# Arduino_Basic_Sensor_Board.net
KiCad netlist of a schematic drawn in EAGLE
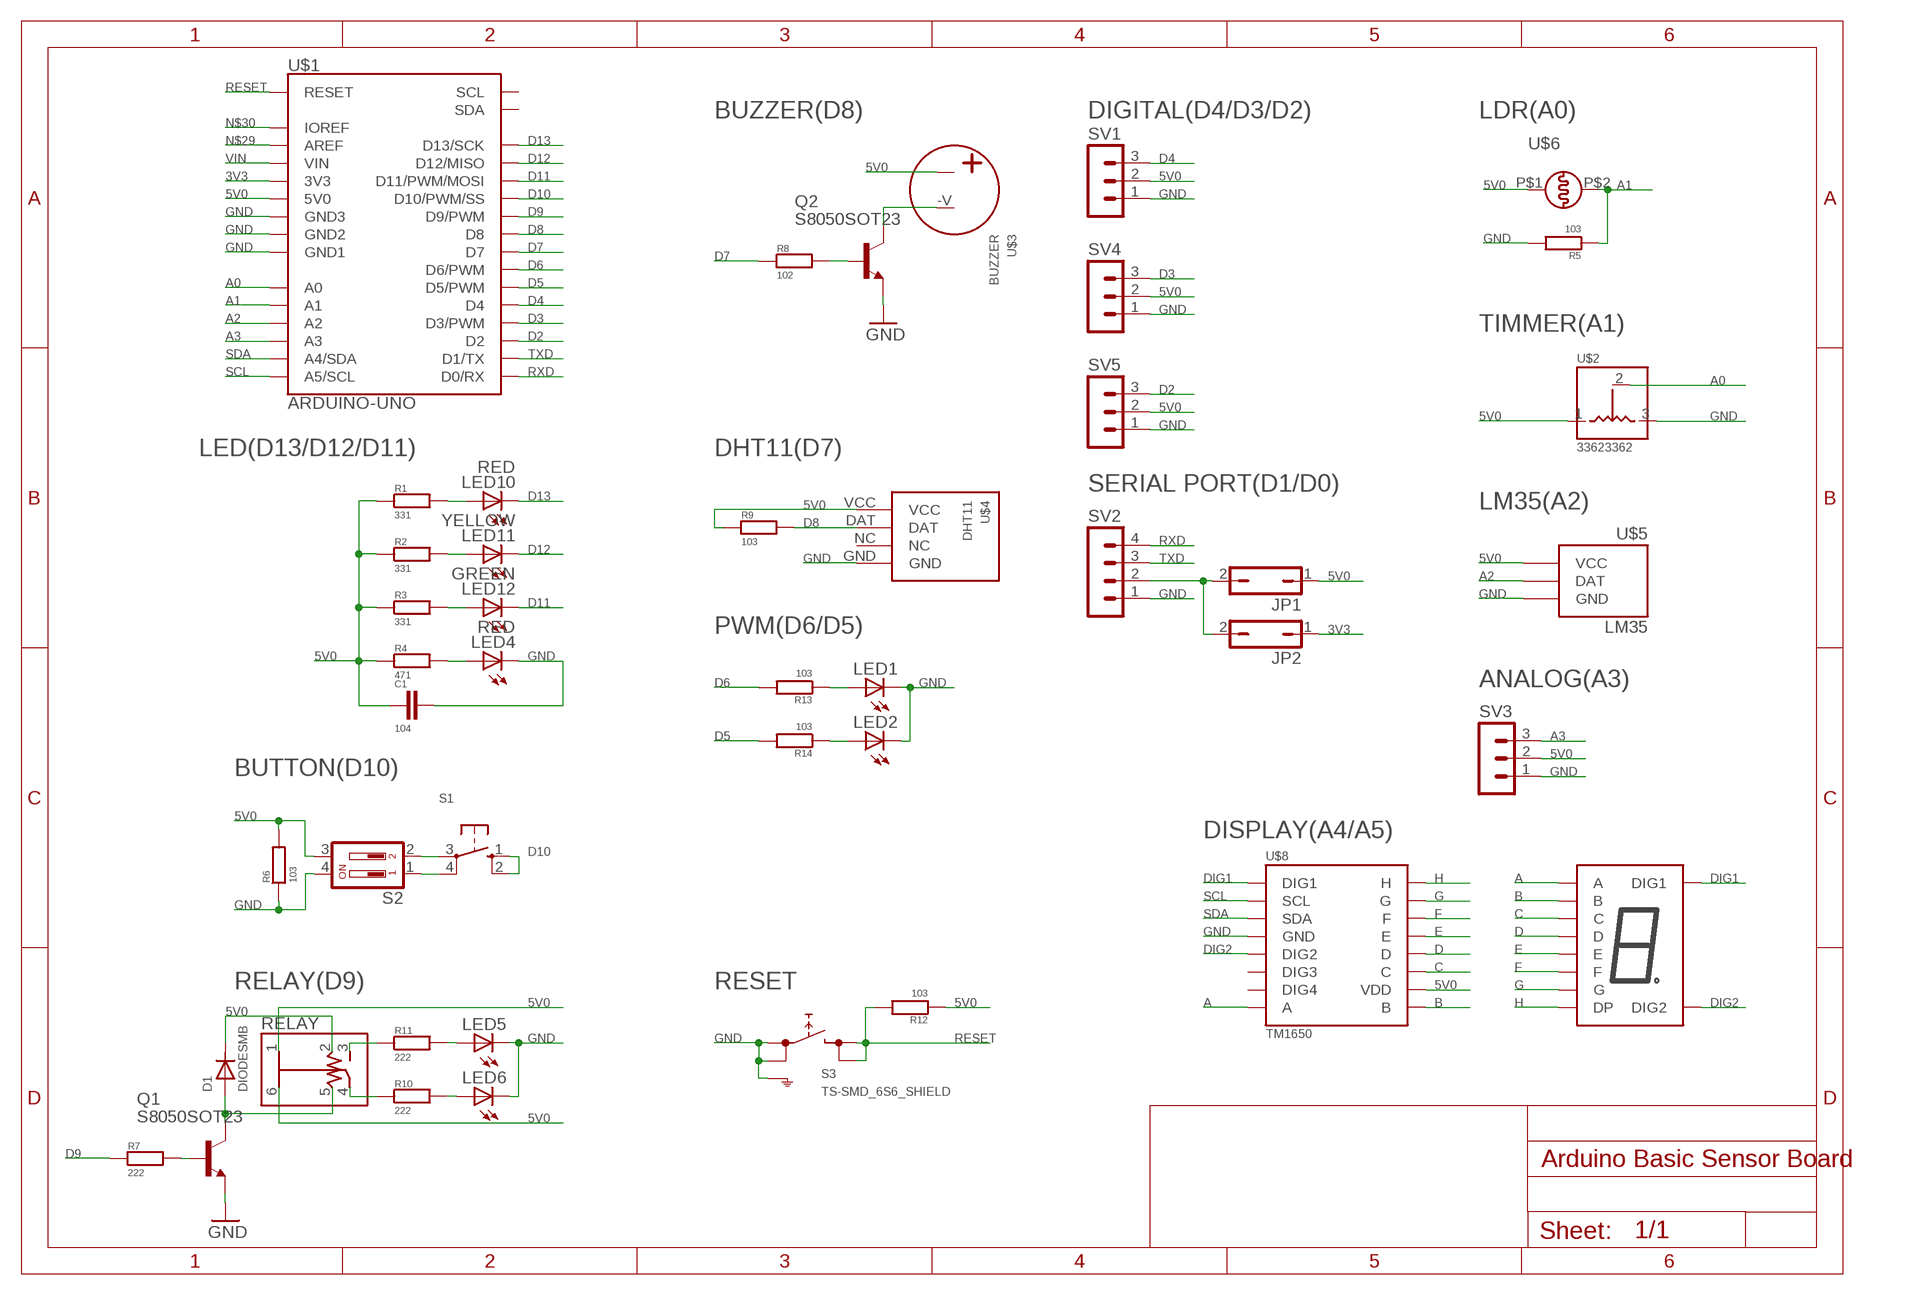
[diagram p0: schematic, sheet 1]

(export (version "E")
  (design (tool "Eeschema 10.0.6"))
  (components
    (comp (ref "C1")
      (value "104")
      (footprint "eagle-import:C0805")
      (libsource (lib "eagle-import") (part "C0805"))
    )
    (comp (ref "D1")
      (value "DIODESMB")
      (footprint "eagle-import:SMB")
      (libsource (lib "eagle-import") (part "DIODESMB"))
    )
    (comp (ref "JP1")
      (value "JP1Q")
      (footprint "eagle-import:JP1Q")
      (libsource (lib "eagle-import") (part "JP1Q"))
    )
    (comp (ref "JP2")
      (value "JP1Q")
      (footprint "eagle-import:JP1Q")
      (libsource (lib "eagle-import") (part "JP1Q"))
    )
    (comp (ref "LED1")
      (value "LEDCHIPLED_1206")
      (footprint "eagle-import:LED1206")
      (libsource (lib "eagle-import") (part "LEDCHIPLED_1206"))
    )
    (comp (ref "LED2")
      (value "LEDCHIPLED_1206")
      (footprint "eagle-import:LED1206")
      (libsource (lib "eagle-import") (part "LEDCHIPLED_1206"))
    )
    (comp (ref "LED4")
      (value "RED")
      (footprint "eagle-import:LED0805")
      (libsource (lib "eagle-import") (part "LEDCHIPLED_0805"))
    )
    (comp (ref "LED5")
      (value "LEDSML1206")
      (footprint "eagle-import:SML1206")
      (libsource (lib "eagle-import") (part "LEDSML1206"))
    )
    (comp (ref "LED6")
      (value "LEDSML1206")
      (footprint "eagle-import:SML1206")
      (libsource (lib "eagle-import") (part "LEDSML1206"))
    )
    (comp (ref "LED10")
      (value "RED")
      (footprint "eagle-import:SML1206")
      (libsource (lib "eagle-import") (part "LEDSML1206"))
    )
    (comp (ref "LED11")
      (value "YELLOW")
      (footprint "eagle-import:SML1206")
      (libsource (lib "eagle-import") (part "LEDSML1206"))
    )
    (comp (ref "LED12")
      (value "GREEN")
      (footprint "eagle-import:SML1206")
      (libsource (lib "eagle-import") (part "LEDSML1206"))
    )
    (comp (ref "Q1")
      (value "S8050SOT23")
      (footprint "eagle-import:SOT23")
      (libsource (lib "eagle-import") (part "S8050SOT23"))
    )
    (comp (ref "Q2")
      (value "S8050SOT23")
      (footprint "eagle-import:SOT23")
      (libsource (lib "eagle-import") (part "S8050SOT23"))
    )
    (comp (ref "R1")
      (value "331")
      (footprint "eagle-import:R0805")
      (libsource (lib "eagle-import") (part "R0805"))
    )
    (comp (ref "R2")
      (value "331")
      (footprint "eagle-import:R0805")
      (libsource (lib "eagle-import") (part "R0805"))
    )
    (comp (ref "R3")
      (value "331")
      (footprint "eagle-import:R0805")
      (libsource (lib "eagle-import") (part "R0805"))
    )
    (comp (ref "R4")
      (value "471")
      (footprint "eagle-import:R0805")
      (libsource (lib "eagle-import") (part "R0805"))
    )
    (comp (ref "R5")
      (value "103")
      (footprint "eagle-import:R0805")
      (libsource (lib "eagle-import") (part "R0805"))
    )
    (comp (ref "R6")
      (value "103")
      (footprint "eagle-import:R0805")
      (libsource (lib "eagle-import") (part "R0805"))
    )
    (comp (ref "R7")
      (value "222")
      (footprint "eagle-import:R0805")
      (libsource (lib "eagle-import") (part "R0805"))
    )
    (comp (ref "R8")
      (value "102")
      (footprint "eagle-import:R0805")
      (libsource (lib "eagle-import") (part "R0805"))
    )
    (comp (ref "R9")
      (value "103")
      (footprint "eagle-import:R0805")
      (libsource (lib "eagle-import") (part "R0805"))
    )
    (comp (ref "R10")
      (value "222")
      (footprint "eagle-import:R0805")
      (libsource (lib "eagle-import") (part "R0805"))
    )
    (comp (ref "R11")
      (value "222")
      (footprint "eagle-import:R0805")
      (libsource (lib "eagle-import") (part "R0805"))
    )
    (comp (ref "R12")
      (value "103")
      (footprint "eagle-import:R0805")
      (libsource (lib "eagle-import") (part "R0805"))
    )
    (comp (ref "R13")
      (value "103")
      (footprint "eagle-import:R0805")
      (libsource (lib "eagle-import") (part "R0805"))
    )
    (comp (ref "R14")
      (value "103")
      (footprint "eagle-import:R0805")
      (libsource (lib "eagle-import") (part "R0805"))
    )
    (comp (ref "RELAY")
      (value "RELAY-HK4100F-DC5V")
      (footprint "eagle-import:RELAY-HK4100F-DC5V")
      (libsource (lib "eagle-import") (part "RELAY-HK4100F-DC5V"))
    )
    (comp (ref "S1")
      (value "TS-DIP-4.54.5")
      (footprint "eagle-import:TS-DIP-4.5_4.5")
      (fields (field (name "MPN") "B3F-1000"))
      (libsource (lib "eagle-import") (part "TS-DIP-4.54.5"))
    )
    (comp (ref "S2")
      (value "SD4-02")
      (footprint "eagle-import:SD4-02")
      (libsource (lib "eagle-import") (part "SD4-02"))
    )
    (comp (ref "S3")
      (value "TS-SMD_6S6_SHIELD")
      (footprint "eagle-import:TS-SMD_6_6_SHIELD")
      (libsource (lib "eagle-import") (part "TS-SMD_66_SHIELDS"))
    )
    (comp (ref "SV1")
      (value "MA03-1")
      (footprint "eagle-import:MA03-1")
      (libsource (lib "eagle-import") (part "MA03-1"))
    )
    (comp (ref "SV2")
      (value "MA04-1")
      (footprint "eagle-import:MA04-1")
      (libsource (lib "eagle-import") (part "MA04-1"))
    )
    (comp (ref "SV3")
      (value "MA03-1")
      (footprint "eagle-import:MA03-1")
      (libsource (lib "eagle-import") (part "MA03-1"))
    )
    (comp (ref "SV4")
      (value "MA03-1")
      (footprint "eagle-import:MA03-1")
      (libsource (lib "eagle-import") (part "MA03-1"))
    )
    (comp (ref "SV5")
      (value "MA03-1")
      (footprint "eagle-import:MA03-1")
      (libsource (lib "eagle-import") (part "MA03-1"))
    )
    (comp (ref "U$1")
      (value "ARDUINO-UNO")
      (footprint "eagle-import:ARDUINO-UNO")
      (libsource (lib "eagle-import") (part "ARDUINO-UNO"))
    )
    (comp (ref "U$2")
      (value "33623362")
      (footprint "eagle-import:3362")
      (libsource (lib "eagle-import") (part "33623362"))
    )
    (comp (ref "U$3")
      (value "BUZZER")
      (footprint "eagle-import:BUZZER")
      (libsource (lib "eagle-import") (part "BUZZER"))
    )
    (comp (ref "U$4")
      (value "DHT11")
      (footprint "eagle-import:DHT11")
      (libsource (lib "eagle-import") (part "DHT11"))
    )
    (comp (ref "U$5")
      (value "LM35")
      (footprint "eagle-import:TO92")
      (libsource (lib "eagle-import") (part "LM35"))
    )
    (comp (ref "U$6")
      (value "LDR")
      (footprint "eagle-import:LDR")
      (libsource (lib "eagle-import") (part "LDR"))
    )
    (comp (ref "U$8")
      (value "TM1650")
      (footprint "eagle-import:SO16")
      (libsource (lib "eagle-import") (part "TM1650"))
    )
    (comp (ref "U$15")
      (value "3261AS")
      (footprint "eagle-import:TN_AS_2_0.36INCH")
      (libsource (lib "eagle-import") (part "3261AS"))
    )
  )
  (nets
    (net (code "1") (name "/3V3") (class "Default")
      (node (ref "JP2") (pin "1") (pinfunction "1_1") (pintype "passive"))
      (node (ref "U$1") (pin "3V3") (pinfunction "3V3_3V3") (pintype "bidirectional"))
    )
    (net (code "2") (name "/5V0") (class "Default")
      (node (ref "C1") (pin "2") (pinfunction "2_2") (pintype "bidirectional"))
      (node (ref "D1") (pin "1") (pinfunction "1_1") (pintype "bidirectional"))
      (node (ref "JP1") (pin "1") (pinfunction "1_1") (pintype "passive"))
      (node (ref "R1") (pin "1") (pinfunction "1_1") (pintype "bidirectional"))
      (node (ref "R12") (pin "1") (pinfunction "1_1") (pintype "bidirectional"))
      (node (ref "R2") (pin "1") (pinfunction "1_1") (pintype "bidirectional"))
      (node (ref "R3") (pin "1") (pinfunction "1_1") (pintype "bidirectional"))
      (node (ref "R4") (pin "1") (pinfunction "1_1") (pintype "bidirectional"))
      (node (ref "R6") (pin "2") (pinfunction "2_2") (pintype "bidirectional"))
      (node (ref "R9") (pin "1") (pinfunction "1_1") (pintype "bidirectional"))
      (node (ref "RELAY") (pin "1") (pinfunction "1_1") (pintype "bidirectional"))
      (node (ref "RELAY") (pin "2") (pinfunction "2_2") (pintype "bidirectional"))
      (node (ref "RELAY") (pin "6") (pinfunction "6_6") (pintype "bidirectional"))
      (node (ref "S2") (pin "3") (pinfunction "3_3") (pintype "passive"))
      (node (ref "SV1") (pin "2") (pinfunction "2_2") (pintype "passive"))
      (node (ref "SV3") (pin "2") (pinfunction "2_2") (pintype "passive"))
      (node (ref "SV4") (pin "2") (pinfunction "2_2") (pintype "passive"))
      (node (ref "SV5") (pin "2") (pinfunction "2_2") (pintype "passive"))
      (node (ref "U$1") (pin "5V0") (pinfunction "5V0_5V0") (pintype "bidirectional"))
      (node (ref "U$2") (pin "1") (pinfunction "1_1") (pintype "bidirectional"))
      (node (ref "U$3") (pin "+V") (pinfunction "+V_+V") (pintype "bidirectional"))
      (node (ref "U$4") (pin "VCC") (pinfunction "VCC_VCC") (pintype "bidirectional"))
      (node (ref "U$5") (pin "1") (pinfunction "VCC_1") (pintype "bidirectional"))
      (node (ref "U$6") (pin "P$1") (pinfunction "P$1_P$1") (pintype "bidirectional"))
      (node (ref "U$8") (pin "10") (pinfunction "VDD_10") (pintype "bidirectional"))
    )
    (net (code "3") (name "/A") (class "Default")
      (node (ref "U$15") (pin "3") (pinfunction "A_3") (pintype "bidirectional"))
      (node (ref "U$8") (pin "8") (pinfunction "A_8") (pintype "bidirectional"))
    )
    (net (code "4") (name "/A0") (class "Default")
      (node (ref "U$1") (pin "A0") (pinfunction "A0_A0") (pintype "bidirectional"))
      (node (ref "U$2") (pin "2") (pinfunction "2_2") (pintype "bidirectional"))
    )
    (net (code "5") (name "/A1") (class "Default")
      (node (ref "R5") (pin "1") (pinfunction "1_1") (pintype "bidirectional"))
      (node (ref "U$1") (pin "A1") (pinfunction "A1_A1") (pintype "bidirectional"))
      (node (ref "U$6") (pin "P$2") (pinfunction "P$2_P$2") (pintype "bidirectional"))
    )
    (net (code "6") (name "/A2") (class "Default")
      (node (ref "U$1") (pin "A2") (pinfunction "A2_A2") (pintype "bidirectional"))
      (node (ref "U$5") (pin "2") (pinfunction "DAT_2") (pintype "bidirectional"))
    )
    (net (code "7") (name "/A3") (class "Default")
      (node (ref "SV3") (pin "3") (pinfunction "3_3") (pintype "passive"))
      (node (ref "U$1") (pin "A3") (pinfunction "A3_A3") (pintype "bidirectional"))
    )
    (net (code "8") (name "/B") (class "Default")
      (node (ref "U$15") (pin "9") (pinfunction "B_9") (pintype "bidirectional"))
      (node (ref "U$8") (pin "9") (pinfunction "B_9") (pintype "bidirectional"))
    )
    (net (code "9") (name "/C") (class "Default")
      (node (ref "U$15") (pin "8") (pinfunction "C_8") (pintype "bidirectional"))
      (node (ref "U$8") (pin "11") (pinfunction "C_11") (pintype "bidirectional"))
    )
    (net (code "10") (name "/D") (class "Default")
      (node (ref "U$15") (pin "6") (pinfunction "D_6") (pintype "bidirectional"))
      (node (ref "U$8") (pin "12") (pinfunction "D_12") (pintype "bidirectional"))
    )
    (net (code "11") (name "/D2") (class "Default")
      (node (ref "SV5") (pin "3") (pinfunction "3_3") (pintype "passive"))
      (node (ref "U$1") (pin "D2") (pinfunction "D2_D2") (pintype "bidirectional"))
    )
    (net (code "12") (name "/D3") (class "Default")
      (node (ref "SV4") (pin "3") (pinfunction "3_3") (pintype "passive"))
      (node (ref "U$1") (pin "D3") (pinfunction "D3/PWM_D3") (pintype "bidirectional"))
    )
    (net (code "13") (name "/D4") (class "Default")
      (node (ref "SV1") (pin "3") (pinfunction "3_3") (pintype "passive"))
      (node (ref "U$1") (pin "D4") (pinfunction "D4_D4") (pintype "bidirectional"))
    )
    (net (code "14") (name "/D5") (class "Default")
      (node (ref "R14") (pin "2") (pinfunction "2_2") (pintype "bidirectional"))
      (node (ref "U$1") (pin "D5") (pinfunction "D5/PWM_D5") (pintype "bidirectional"))
    )
    (net (code "15") (name "/D6") (class "Default")
      (node (ref "R13") (pin "2") (pinfunction "2_2") (pintype "bidirectional"))
      (node (ref "U$1") (pin "D6") (pinfunction "D6/PWM_D6") (pintype "bidirectional"))
    )
    (net (code "16") (name "/D7") (class "Default")
      (node (ref "R8") (pin "1") (pinfunction "1_1") (pintype "bidirectional"))
      (node (ref "U$1") (pin "D7") (pinfunction "D7_D7") (pintype "bidirectional"))
    )
    (net (code "17") (name "/D8") (class "Default")
      (node (ref "R9") (pin "2") (pinfunction "2_2") (pintype "bidirectional"))
      (node (ref "U$1") (pin "D8") (pinfunction "D8_D8") (pintype "bidirectional"))
      (node (ref "U$4") (pin "DAT") (pinfunction "DAT_DAT") (pintype "bidirectional"))
    )
    (net (code "18") (name "/D9") (class "Default")
      (node (ref "R7") (pin "1") (pinfunction "1_1") (pintype "bidirectional"))
      (node (ref "U$1") (pin "D9") (pinfunction "D9/PWM_D9") (pintype "bidirectional"))
    )
    (net (code "19") (name "/D10") (class "Default")
      (node (ref "S1") (pin "1") (pinfunction "S_1") (pintype "passive"))
      (node (ref "S1") (pin "2") (pinfunction "S1_2") (pintype "passive"))
      (node (ref "U$1") (pin "D10") (pinfunction "D10/PWM/SS_D10") (pintype "bidirectional"))
    )
    (net (code "20") (name "/D11") (class "Default")
      (node (ref "LED12") (pin "C") (pinfunction "C_C") (pintype "passive"))
      (node (ref "U$1") (pin "D11") (pinfunction "D11/PWM/MOSI_D11") (pintype "bidirectional"))
    )
    (net (code "21") (name "/D12") (class "Default")
      (node (ref "LED11") (pin "C") (pinfunction "C_C") (pintype "passive"))
      (node (ref "U$1") (pin "D12") (pinfunction "D12/MISO_D12") (pintype "bidirectional"))
    )
    (net (code "22") (name "/D13") (class "Default")
      (node (ref "LED10") (pin "C") (pinfunction "C_C") (pintype "passive"))
      (node (ref "U$1") (pin "D13") (pinfunction "D13/SCK_D13") (pintype "bidirectional"))
    )
    (net (code "23") (name "/DIG1") (class "Default")
      (node (ref "U$15") (pin "10") (pinfunction "DIG1_10") (pintype "bidirectional"))
      (node (ref "U$8") (pin "1") (pinfunction "DIG1_1") (pintype "bidirectional"))
    )
    (net (code "24") (name "/DIG2") (class "Default")
      (node (ref "U$15") (pin "5") (pinfunction "DIG2_5") (pintype "bidirectional"))
      (node (ref "U$8") (pin "5") (pinfunction "DIG2_5") (pintype "bidirectional"))
    )
    (net (code "25") (name "/E") (class "Default")
      (node (ref "U$15") (pin "7") (pinfunction "E_7") (pintype "bidirectional"))
      (node (ref "U$8") (pin "13") (pinfunction "E_13") (pintype "bidirectional"))
    )
    (net (code "26") (name "/F") (class "Default")
      (node (ref "U$15") (pin "4") (pinfunction "F_4") (pintype "bidirectional"))
      (node (ref "U$8") (pin "14") (pinfunction "F_14") (pintype "bidirectional"))
    )
    (net (code "27") (name "/G") (class "Default")
      (node (ref "U$15") (pin "1") (pinfunction "G_1") (pintype "bidirectional"))
      (node (ref "U$8") (pin "15") (pinfunction "G_15") (pintype "bidirectional"))
    )
    (net (code "28") (name "/H") (class "Default")
      (node (ref "U$15") (pin "2") (pinfunction "DP_2") (pintype "bidirectional"))
      (node (ref "U$8") (pin "16") (pinfunction "H_16") (pintype "bidirectional"))
    )
    (net (code "29") (name "/N$29") (class "Default")
      (node (ref "U$1") (pin "AREF") (pinfunction "AREF_AREF") (pintype "bidirectional"))
    )
    (net (code "30") (name "/N$30") (class "Default")
      (node (ref "U$1") (pin "REF") (pinfunction "IOREF_REF") (pintype "bidirectional"))
    )
    (net (code "31") (name "/RESET") (class "Default")
      (node (ref "R12") (pin "2") (pinfunction "2_2") (pintype "bidirectional"))
      (node (ref "S3") (pin "3") (pinfunction "2.1_3") (pintype "passive"))
      (node (ref "S3") (pin "4") (pinfunction "2.2_4") (pintype "passive"))
      (node (ref "U$1") (pin "RST") (pinfunction "RESET_RST") (pintype "bidirectional"))
    )
    (net (code "32") (name "/RXD") (class "Default")
      (node (ref "SV2") (pin "4") (pinfunction "4_4") (pintype "passive"))
      (node (ref "U$1") (pin "D0") (pinfunction "D0/RX_D0") (pintype "bidirectional"))
    )
    (net (code "33") (name "/SCL") (class "Default")
      (node (ref "U$1") (pin "A5") (pinfunction "A5/SCL_A5") (pintype "bidirectional"))
      (node (ref "U$8") (pin "2") (pinfunction "SCL_2") (pintype "bidirectional"))
    )
    (net (code "34") (name "/SDA") (class "Default")
      (node (ref "U$1") (pin "A4") (pinfunction "A4/SDA_A4") (pintype "bidirectional"))
      (node (ref "U$8") (pin "3") (pinfunction "SDA_3") (pintype "bidirectional"))
    )
    (net (code "35") (name "/TXD") (class "Default")
      (node (ref "SV2") (pin "3") (pinfunction "3_3") (pintype "passive"))
      (node (ref "U$1") (pin "D1") (pinfunction "D1/TX_D1") (pintype "bidirectional"))
    )
    (net (code "36") (name "/VIN") (class "Default")
      (node (ref "U$1") (pin "VIN") (pinfunction "VIN_VIN") (pintype "bidirectional"))
    )
    (net (code "37") (name "GND") (class "Default")
      (node (ref "C1") (pin "1") (pinfunction "1_1") (pintype "bidirectional"))
      (node (ref "LED1") (pin "C") (pinfunction "C_C") (pintype "passive"))
      (node (ref "LED2") (pin "C") (pinfunction "C_C") (pintype "passive"))
      (node (ref "LED4") (pin "C") (pinfunction "C_C") (pintype "passive"))
      (node (ref "LED5") (pin "C") (pinfunction "C_C") (pintype "passive"))
      (node (ref "LED6") (pin "C") (pinfunction "C_C") (pintype "passive"))
      (node (ref "Q1") (pin "E") (pinfunction "E_E") (pintype "passive"))
      (node (ref "Q2") (pin "E") (pinfunction "E_E") (pintype "passive"))
      (node (ref "R5") (pin "2") (pinfunction "2_2") (pintype "bidirectional"))
      (node (ref "R6") (pin "1") (pinfunction "1_1") (pintype "bidirectional"))
      (node (ref "S2") (pin "4") (pinfunction "4_4") (pintype "passive"))
      (node (ref "S3") (pin "1") (pinfunction "1.1_1") (pintype "passive"))
      (node (ref "S3") (pin "2") (pinfunction "1.2_2") (pintype "passive"))
      (node (ref "S3") (pin "5") (pinfunction "SH_5") (pintype "passive"))
      (node (ref "SV1") (pin "1") (pinfunction "1_1") (pintype "passive"))
      (node (ref "SV2") (pin "1") (pinfunction "1_1") (pintype "passive"))
      (node (ref "SV3") (pin "1") (pinfunction "1_1") (pintype "passive"))
      (node (ref "SV4") (pin "1") (pinfunction "1_1") (pintype "passive"))
      (node (ref "SV5") (pin "1") (pinfunction "1_1") (pintype "passive"))
      (node (ref "U$1") (pin "GND1") (pinfunction "GND1_GND1") (pintype "bidirectional"))
      (node (ref "U$1") (pin "GND2") (pinfunction "GND2_GND2") (pintype "bidirectional"))
      (node (ref "U$1") (pin "GND3") (pinfunction "GND3_GND3") (pintype "bidirectional"))
      (node (ref "U$2") (pin "3") (pinfunction "3_3") (pintype "bidirectional"))
      (node (ref "U$4") (pin "GND") (pinfunction "GND_GND") (pintype "bidirectional"))
      (node (ref "U$5") (pin "3") (pinfunction "GND_3") (pintype "bidirectional"))
      (node (ref "U$8") (pin "4") (pinfunction "GND_4") (pintype "bidirectional"))
    )
    (net (code "38") (name "Net-(D1-Pad2)") (class "Default")
      (node (ref "D1") (pin "2") (pinfunction "2_2") (pintype "bidirectional"))
      (node (ref "Q1") (pin "C") (pinfunction "C_C") (pintype "passive"))
      (node (ref "RELAY") (pin "5") (pinfunction "5_5") (pintype "bidirectional"))
    )
    (net (code "39") (name "Net-(JP1-Pad2)") (class "Default")
      (node (ref "JP1") (pin "2") (pinfunction "2_2") (pintype "passive"))
      (node (ref "JP2") (pin "2") (pinfunction "2_2") (pintype "passive"))
      (node (ref "SV2") (pin "2") (pinfunction "2_2") (pintype "passive"))
    )
    (net (code "40") (name "Net-(LED1-PadA)") (class "Default")
      (node (ref "LED1") (pin "A") (pinfunction "A_A") (pintype "passive"))
      (node (ref "R13") (pin "1") (pinfunction "1_1") (pintype "bidirectional"))
    )
    (net (code "41") (name "Net-(LED2-PadA)") (class "Default")
      (node (ref "LED2") (pin "A") (pinfunction "A_A") (pintype "passive"))
      (node (ref "R14") (pin "1") (pinfunction "1_1") (pintype "bidirectional"))
    )
    (net (code "42") (name "Net-(LED4-PadA)") (class "Default")
      (node (ref "LED4") (pin "A") (pinfunction "A_A") (pintype "passive"))
      (node (ref "R4") (pin "2") (pinfunction "2_2") (pintype "bidirectional"))
    )
    (net (code "43") (name "Net-(LED5-PadA)") (class "Default")
      (node (ref "LED5") (pin "A") (pinfunction "A_A") (pintype "passive"))
      (node (ref "R11") (pin "2") (pinfunction "2_2") (pintype "bidirectional"))
    )
    (net (code "44") (name "Net-(LED6-PadA)") (class "Default")
      (node (ref "LED6") (pin "A") (pinfunction "A_A") (pintype "passive"))
      (node (ref "R10") (pin "2") (pinfunction "2_2") (pintype "bidirectional"))
    )
    (net (code "45") (name "Net-(LED10-PadA)") (class "Default")
      (node (ref "LED10") (pin "A") (pinfunction "A_A") (pintype "passive"))
      (node (ref "R1") (pin "2") (pinfunction "2_2") (pintype "bidirectional"))
    )
    (net (code "46") (name "Net-(LED11-PadA)") (class "Default")
      (node (ref "LED11") (pin "A") (pinfunction "A_A") (pintype "passive"))
      (node (ref "R2") (pin "2") (pinfunction "2_2") (pintype "bidirectional"))
    )
    (net (code "47") (name "Net-(LED12-PadA)") (class "Default")
      (node (ref "LED12") (pin "A") (pinfunction "A_A") (pintype "passive"))
      (node (ref "R3") (pin "2") (pinfunction "2_2") (pintype "bidirectional"))
    )
    (net (code "48") (name "Net-(Q1-PadB)") (class "Default")
      (node (ref "Q1") (pin "B") (pinfunction "B_B") (pintype "passive"))
      (node (ref "R7") (pin "2") (pinfunction "2_2") (pintype "bidirectional"))
    )
    (net (code "49") (name "Net-(Q2-PadB)") (class "Default")
      (node (ref "Q2") (pin "B") (pinfunction "B_B") (pintype "passive"))
      (node (ref "R8") (pin "2") (pinfunction "2_2") (pintype "bidirectional"))
    )
    (net (code "50") (name "Net-(Q2-PadC)") (class "Default")
      (node (ref "Q2") (pin "C") (pinfunction "C_C") (pintype "passive"))
      (node (ref "U$3") (pin "-V") (pinfunction "-V_-V") (pintype "bidirectional"))
    )
    (net (code "51") (name "Net-(R10-Pad1)") (class "Default")
      (node (ref "R10") (pin "1") (pinfunction "1_1") (pintype "bidirectional"))
      (node (ref "RELAY") (pin "4") (pinfunction "4_4") (pintype "bidirectional"))
    )
    (net (code "52") (name "Net-(R11-Pad1)") (class "Default")
      (node (ref "R11") (pin "1") (pinfunction "1_1") (pintype "bidirectional"))
      (node (ref "RELAY") (pin "3") (pinfunction "3_3") (pintype "bidirectional"))
    )
    (net (code "53") (name "Net-(S1-P)") (class "Default")
      (node (ref "S1") (pin "3") (pinfunction "P_3") (pintype "passive"))
      (node (ref "S2") (pin "2") (pinfunction "2_2") (pintype "passive"))
    )
    (net (code "54") (name "Net-(S1-P1)") (class "Default")
      (node (ref "S1") (pin "4") (pinfunction "P1_4") (pintype "passive"))
      (node (ref "S2") (pin "1") (pinfunction "1_1") (pintype "passive"))
    )
    (net (code "55") (name "unconnected-(U$1-PadSCL)") (class "Default")
      (node (ref "U$1") (pin "SCL") (pinfunction "SCL_SCL") (pintype "bidirectional"))
    )
    (net (code "56") (name "unconnected-(U$1-PadSDA)") (class "Default")
      (node (ref "U$1") (pin "SDA") (pinfunction "SDA_SDA") (pintype "bidirectional"))
    )
    (net (code "57") (name "unconnected-(U$4-PadNC)") (class "Default")
      (node (ref "U$4") (pin "NC") (pinfunction "NC_NC") (pintype "bidirectional"))
    )
    (net (code "58") (name "unconnected-(U$8-DIG3-Pad6)") (class "Default")
      (node (ref "U$8") (pin "6") (pinfunction "DIG3_6") (pintype "bidirectional"))
    )
    (net (code "59") (name "unconnected-(U$8-DIG4-Pad7)") (class "Default")
      (node (ref "U$8") (pin "7") (pinfunction "DIG4_7") (pintype "bidirectional"))
    )
  )
)
